# Wykonana.net
KiCad netlist of a schematic drawn in EAGLE
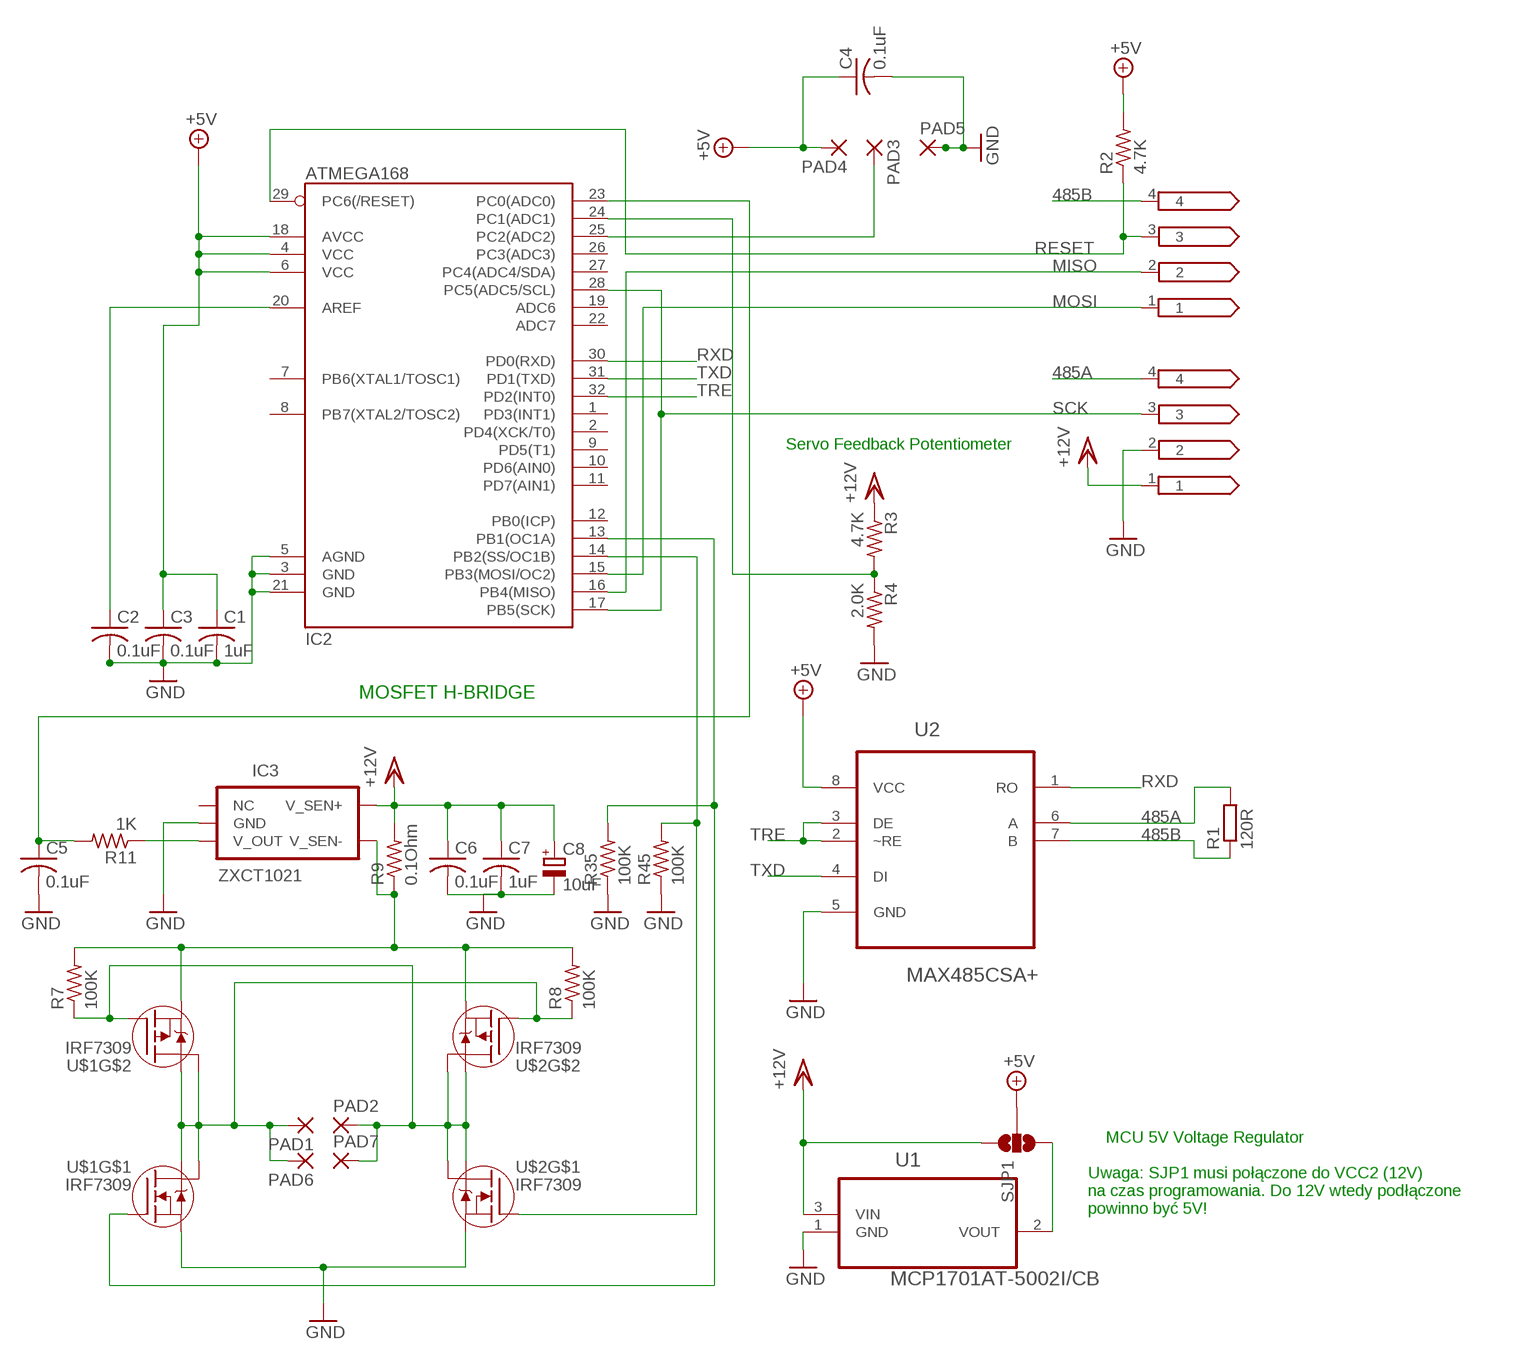
[diagram p0: schematic, sheet 1]

(export (version "E")
  (design (tool "Eeschema 10.0.6"))
  (components
    (comp (ref "C1")
      (value "1uF")
      (footprint "eagle-import:C0603")
      (libsource (lib "eagle-import") (part "C-USC0603"))
    )
    (comp (ref "C2")
      (value "0.1uF")
      (footprint "eagle-import:C0603")
      (libsource (lib "eagle-import") (part "C-USC0603"))
    )
    (comp (ref "C3")
      (value "0.1uF")
      (footprint "eagle-import:C0603")
      (libsource (lib "eagle-import") (part "C-USC0603"))
    )
    (comp (ref "C4")
      (value "0.1uF")
      (footprint "eagle-import:C0603")
      (libsource (lib "eagle-import") (part "C-USC0603"))
    )
    (comp (ref "C5")
      (value "0.1uF")
      (footprint "eagle-import:C0603K")
      (libsource (lib "eagle-import") (part "C-USC0603K"))
    )
    (comp (ref "C6")
      (value "0.1uF")
      (footprint "eagle-import:C0603")
      (libsource (lib "eagle-import") (part "C-USC0603"))
    )
    (comp (ref "C7")
      (value "1uF")
      (footprint "eagle-import:C0603")
      (libsource (lib "eagle-import") (part "C-USC0603"))
    )
    (comp (ref "C8")
      (value "10uF")
      (footprint "eagle-import:A_3216-18R")
      (libsource (lib "eagle-import") (part "CPOL-EUA/3216-18R"))
    )
    (comp (ref "IC2")
      (value "ATMEGA168")
      (footprint "eagle-import:TQFP32-08")
      (libsource (lib "eagle-import") (part "ATMEGA168"))
    )
    (comp (ref "IC3")
      (value "ZXCT1021")
      (footprint "eagle-import:SOT23-5")
      (libsource (lib "eagle-import") (part "ZXCT1021SOT23-5"))
    )
    (comp (ref "JP1")
      (value "4-EDGEVERSION2")
      (footprint "eagle-import:4-PIN-EDGE-V2")
      (libsource (lib "eagle-import") (part "4-EDGEVERSION2"))
    )
    (comp (ref "JP2")
      (value "4-EDGEVERSION2")
      (footprint "eagle-import:4-PIN-EDGE-V2")
      (libsource (lib "eagle-import") (part "4-EDGEVERSION2"))
    )
    (comp (ref "PAD1")
      (value "2,15/1,0")
      (footprint "eagle-import:2,15_1,0")
      (libsource (lib "eagle-import") (part "2,15/1,0"))
    )
    (comp (ref "PAD2")
      (value "2,15/1,0")
      (footprint "eagle-import:2,15_1,0")
      (libsource (lib "eagle-import") (part "2,15/1,0"))
    )
    (comp (ref "PAD3")
      (value "1,6/0,8")
      (footprint "eagle-import:1,6_0,8")
      (libsource (lib "eagle-import") (part "1,6/0,8"))
    )
    (comp (ref "PAD4")
      (value "1,6/0,8")
      (footprint "eagle-import:1,6_0,8")
      (libsource (lib "eagle-import") (part "1,6/0,8"))
    )
    (comp (ref "PAD5")
      (value "1,6/0,8")
      (footprint "eagle-import:1,6_0,8")
      (libsource (lib "eagle-import") (part "1,6/0,8"))
    )
    (comp (ref "PAD6")
      (value "2,15/1,0")
      (footprint "eagle-import:2,15_1,0")
      (libsource (lib "eagle-import") (part "2,15/1,0"))
    )
    (comp (ref "PAD7")
      (value "2,15/1,0")
      (footprint "eagle-import:2,15_1,0")
      (libsource (lib "eagle-import") (part "2,15/1,0"))
    )
    (comp (ref "R1")
      (value "120R")
      (footprint "eagle-import:R0603")
      (libsource (lib "eagle-import") (part "R-EU_R0603"))
    )
    (comp (ref "R2")
      (value "4.7K")
      (footprint "eagle-import:R0603")
      (libsource (lib "eagle-import") (part "R-US_R0603"))
    )
    (comp (ref "R3")
      (value "4.7K")
      (footprint "eagle-import:R0603")
      (libsource (lib "eagle-import") (part "R-US_R0603"))
    )
    (comp (ref "R4")
      (value "2.0K")
      (footprint "eagle-import:R0603")
      (libsource (lib "eagle-import") (part "R-US_R0603"))
    )
    (comp (ref "R7")
      (value "100K")
      (footprint "eagle-import:R0603")
      (libsource (lib "eagle-import") (part "R-US_R0603"))
    )
    (comp (ref "R8")
      (value "100K")
      (footprint "eagle-import:R0603")
      (libsource (lib "eagle-import") (part "R-US_R0603"))
    )
    (comp (ref "R9")
      (value "0.1Ohm")
      (footprint "eagle-import:R0603")
      (libsource (lib "eagle-import") (part "R-US_R0603"))
    )
    (comp (ref "R11")
      (value "1K")
      (footprint "eagle-import:R0603")
      (libsource (lib "eagle-import") (part "R-US_R0603"))
    )
    (comp (ref "R35")
      (value "100K")
      (footprint "eagle-import:R0603")
      (libsource (lib "eagle-import") (part "R-US_R0603"))
    )
    (comp (ref "R45")
      (value "100K")
      (footprint "eagle-import:R0603")
      (libsource (lib "eagle-import") (part "R-US_R0603"))
    )
    (comp (ref "SJP1")
      (value "SOLDERJUMPER_2WAYPASTE2&3")
      (footprint "eagle-import:SJ_3_PASTE2&3")
      (libsource (lib "eagle-import") (part "SOLDERJUMPER_2WAYPASTE2&3"))
    )
    (comp (ref "U$1")
      (value "IRF7309")
      (footprint "eagle-import:SO8-2")
      (libsource (lib "eagle-import") (part "IRF7309"))
    )
    (comp (ref "U$2")
      (value "IRF7309")
      (footprint "eagle-import:SO8-2")
      (libsource (lib "eagle-import") (part "IRF7309"))
    )
    (comp (ref "U1")
      (value "MCP1701AT-5002I/CB")
      (footprint "eagle-import:SOT95P255X145-3N")
      (libsource (lib "eagle-import") (part "MCP1701AT-5002I/CB"))
    )
    (comp (ref "U2")
      (value "MAX485CSA+")
      (footprint "eagle-import:SOIC127P600X175-8N")
      (libsource (lib "eagle-import") (part "MAX485CSA+"))
    )
  )
  (nets
    (net (code "1") (name "+5V") (class "Default")
      (node (ref "C1") (pin "1") (pinfunction "1_1") (pintype "passive"))
      (node (ref "C3") (pin "1") (pinfunction "1_1") (pintype "passive"))
      (node (ref "C4") (pin "1") (pinfunction "1_1") (pintype "passive"))
      (node (ref "IC2") (pin "18") (pinfunction "AVCC_18") (pintype "bidirectional"))
      (node (ref "IC2") (pin "4") (pinfunction "VCC_4") (pintype "bidirectional"))
      (node (ref "IC2") (pin "6") (pinfunction "VCC_6") (pintype "bidirectional"))
      (node (ref "PAD4") (pin "1") (pinfunction "P_1") (pintype "passive"))
      (node (ref "R2") (pin "2") (pinfunction "2_2") (pintype "passive"))
      (node (ref "SJP1") (pin "2") (pinfunction "2_2") (pintype "passive"))
      (node (ref "U2") (pin "8") (pinfunction "VCC_8") (pintype "power_in"))
    )
    (net (code "2") (name "+12V") (class "Default")
      (node (ref "C6") (pin "1") (pinfunction "1_1") (pintype "passive"))
      (node (ref "C7") (pin "1") (pinfunction "1_1") (pintype "passive"))
      (node (ref "C8") (pin "+") (pinfunction "+_+") (pintype "passive"))
      (node (ref "IC3") (pin "4") (pinfunction "V_SEN+_4") (pintype "input"))
      (node (ref "JP1") (pin "1") (pinfunction "1_1") (pintype "bidirectional"))
      (node (ref "R3") (pin "1") (pinfunction "1_1") (pintype "passive"))
      (node (ref "R9") (pin "2") (pinfunction "2_2") (pintype "passive"))
      (node (ref "SJP1") (pin "1") (pinfunction "1_1") (pintype "passive"))
      (node (ref "U1") (pin "3") (pinfunction "VIN_3") (pintype "input"))
    )
    (net (code "3") (name "/485A") (class "Default")
      (node (ref "JP1") (pin "4") (pinfunction "4_4") (pintype "bidirectional"))
      (node (ref "R1") (pin "2") (pinfunction "2_2") (pintype "passive"))
      (node (ref "U2") (pin "6") (pinfunction "A_6") (pintype "bidirectional"))
    )
    (net (code "4") (name "/485B") (class "Default")
      (node (ref "JP2") (pin "4") (pinfunction "4_4") (pintype "bidirectional"))
      (node (ref "R1") (pin "1") (pinfunction "1_1") (pintype "passive"))
      (node (ref "U2") (pin "7") (pinfunction "B_7") (pintype "bidirectional"))
    )
    (net (code "5") (name "/MISO") (class "Default")
      (node (ref "IC2") (pin "16") (pinfunction "PB4(MISO)_16") (pintype "bidirectional"))
      (node (ref "JP2") (pin "2") (pinfunction "2_2") (pintype "bidirectional"))
    )
    (net (code "6") (name "/MOSI") (class "Default")
      (node (ref "IC2") (pin "15") (pinfunction "PB3(MOSI/OC2)_15") (pintype "bidirectional"))
      (node (ref "JP2") (pin "1") (pinfunction "1_1") (pintype "bidirectional"))
    )
    (net (code "7") (name "/RESET") (class "Default")
      (node (ref "IC2") (pin "29") (pinfunction "PC6(/RESET)_29") (pintype "bidirectional"))
      (node (ref "JP2") (pin "3") (pinfunction "3_3") (pintype "bidirectional"))
      (node (ref "R2") (pin "1") (pinfunction "1_1") (pintype "passive"))
    )
    (net (code "8") (name "/RXD") (class "Default")
      (node (ref "IC2") (pin "30") (pinfunction "PD0(RXD)_30") (pintype "bidirectional"))
      (node (ref "U2") (pin "1") (pinfunction "RO_1") (pintype "output"))
    )
    (net (code "9") (name "/SCK") (class "Default")
      (node (ref "IC2") (pin "17") (pinfunction "PB5(SCK)_17") (pintype "bidirectional"))
      (node (ref "IC2") (pin "28") (pinfunction "PC5(ADC5/SCL)_28") (pintype "bidirectional"))
      (node (ref "JP1") (pin "3") (pinfunction "3_3") (pintype "bidirectional"))
    )
    (net (code "10") (name "/TRE") (class "Default")
      (node (ref "IC2") (pin "32") (pinfunction "PD2(INT0)_32") (pintype "bidirectional"))
      (node (ref "U2") (pin "2") (pinfunction "~{RE}_2") (pintype "input"))
      (node (ref "U2") (pin "3") (pinfunction "DE_3") (pintype "input"))
    )
    (net (code "11") (name "/TXD") (class "Default")
      (node (ref "IC2") (pin "31") (pinfunction "PD1(TXD)_31") (pintype "bidirectional"))
      (node (ref "U2") (pin "4") (pinfunction "DI_4") (pintype "input"))
    )
    (net (code "12") (name "GND") (class "Default")
      (node (ref "C1") (pin "2") (pinfunction "2_2") (pintype "passive"))
      (node (ref "C2") (pin "2") (pinfunction "2_2") (pintype "passive"))
      (node (ref "C3") (pin "2") (pinfunction "2_2") (pintype "passive"))
      (node (ref "C4") (pin "2") (pinfunction "2_2") (pintype "passive"))
      (node (ref "C5") (pin "2") (pinfunction "2_2") (pintype "passive"))
      (node (ref "C6") (pin "2") (pinfunction "2_2") (pintype "passive"))
      (node (ref "C7") (pin "2") (pinfunction "2_2") (pintype "passive"))
      (node (ref "C8") (pin "-") (pinfunction "-_-") (pintype "passive"))
      (node (ref "IC2") (pin "21") (pinfunction "GND_21") (pintype "bidirectional"))
      (node (ref "IC2") (pin "3") (pinfunction "GND_3") (pintype "bidirectional"))
      (node (ref "IC2") (pin "5") (pinfunction "AGND_5") (pintype "bidirectional"))
      (node (ref "IC3") (pin "2") (pinfunction "GND_2") (pintype "input"))
      (node (ref "JP1") (pin "2") (pinfunction "2_2") (pintype "bidirectional"))
      (node (ref "PAD5") (pin "1") (pinfunction "P_1") (pintype "passive"))
      (node (ref "R35") (pin "1") (pinfunction "1_1") (pintype "passive"))
      (node (ref "R4") (pin "2") (pinfunction "2_2") (pintype "passive"))
      (node (ref "R45") (pin "1") (pinfunction "1_1") (pintype "passive"))
      (node (ref "U$1") (pin "1") (pinfunction "S_1") (pintype "bidirectional"))
      (node (ref "U$2") (pin "1") (pinfunction "S_1") (pintype "bidirectional"))
      (node (ref "U1") (pin "1") (pinfunction "GND_1") (pintype "passive"))
      (node (ref "U2") (pin "5") (pinfunction "GND_5") (pintype "passive"))
    )
    (net (code "13") (name "Net-(IC2-AREF)") (class "Default")
      (node (ref "C2") (pin "1") (pinfunction "1_1") (pintype "passive"))
      (node (ref "IC2") (pin "20") (pinfunction "AREF_20") (pintype "bidirectional"))
    )
    (net (code "14") (name "Net-(IC2-PB1(OC1A))") (class "Default")
      (node (ref "IC2") (pin "13") (pinfunction "PB1(OC1A)_13") (pintype "bidirectional"))
      (node (ref "R35") (pin "2") (pinfunction "2_2") (pintype "passive"))
      (node (ref "U$1") (pin "2") (pinfunction "G_2") (pintype "bidirectional"))
    )
    (net (code "15") (name "Net-(IC2-PB2(SS{slash}OC1B))") (class "Default")
      (node (ref "IC2") (pin "14") (pinfunction "PB2(SS/OC1B)_14") (pintype "bidirectional"))
      (node (ref "R45") (pin "2") (pinfunction "2_2") (pintype "passive"))
      (node (ref "U$2") (pin "2") (pinfunction "G_2") (pintype "bidirectional"))
    )
    (net (code "16") (name "Net-(IC2-PC0(ADC0))") (class "Default")
      (node (ref "C5") (pin "1") (pinfunction "1_1") (pintype "passive"))
      (node (ref "IC2") (pin "23") (pinfunction "PC0(ADC0)_23") (pintype "bidirectional"))
      (node (ref "R11") (pin "2") (pinfunction "2_2") (pintype "passive"))
    )
    (net (code "17") (name "Net-(IC2-PC1(ADC1))") (class "Default")
      (node (ref "IC2") (pin "24") (pinfunction "PC1(ADC1)_24") (pintype "bidirectional"))
      (node (ref "R3") (pin "2") (pinfunction "2_2") (pintype "passive"))
      (node (ref "R4") (pin "1") (pinfunction "1_1") (pintype "passive"))
    )
    (net (code "18") (name "Net-(IC2-PC2(ADC2))") (class "Default")
      (node (ref "IC2") (pin "25") (pinfunction "PC2(ADC2)_25") (pintype "bidirectional"))
      (node (ref "PAD3") (pin "1") (pinfunction "P_1") (pintype "passive"))
    )
    (net (code "19") (name "Net-(IC3-V_OUT)") (class "Default")
      (node (ref "IC3") (pin "3") (pinfunction "V_OUT_3") (pintype "input"))
      (node (ref "R11") (pin "1") (pinfunction "1_1") (pintype "passive"))
    )
    (net (code "20") (name "Net-(IC3-V_SEN-)") (class "Default")
      (node (ref "IC3") (pin "5") (pinfunction "V_SEN-_5") (pintype "passive"))
      (node (ref "R7") (pin "2") (pinfunction "2_2") (pintype "passive"))
      (node (ref "R8") (pin "2") (pinfunction "2_2") (pintype "passive"))
      (node (ref "R9") (pin "1") (pinfunction "1_1") (pintype "passive"))
      (node (ref "U$1") (pin "3") (pinfunction "S_3") (pintype "bidirectional"))
      (node (ref "U$2") (pin "3") (pinfunction "S_3") (pintype "bidirectional"))
    )
    (net (code "21") (name "Net-(PAD1-P)") (class "Default")
      (node (ref "PAD1") (pin "1") (pinfunction "P_1") (pintype "passive"))
      (node (ref "PAD6") (pin "1") (pinfunction "P_1") (pintype "passive"))
      (node (ref "R8") (pin "1") (pinfunction "1_1") (pintype "passive"))
      (node (ref "U$1") (pin "5") (pinfunction "D_5") (pintype "bidirectional"))
      (node (ref "U$1") (pin "6") (pinfunction "D_6") (pintype "bidirectional"))
      (node (ref "U$1") (pin "7") (pinfunction "D_7") (pintype "bidirectional"))
      (node (ref "U$1") (pin "8") (pinfunction "D_8") (pintype "bidirectional"))
      (node (ref "U$2") (pin "4") (pinfunction "G_4") (pintype "bidirectional"))
    )
    (net (code "22") (name "Net-(PAD2-P)") (class "Default")
      (node (ref "PAD2") (pin "1") (pinfunction "P_1") (pintype "passive"))
      (node (ref "PAD7") (pin "1") (pinfunction "P_1") (pintype "passive"))
      (node (ref "R7") (pin "1") (pinfunction "1_1") (pintype "passive"))
      (node (ref "U$1") (pin "4") (pinfunction "G_4") (pintype "bidirectional"))
      (node (ref "U$2") (pin "5") (pinfunction "D_5") (pintype "bidirectional"))
      (node (ref "U$2") (pin "6") (pinfunction "D_6") (pintype "bidirectional"))
      (node (ref "U$2") (pin "7") (pinfunction "D_7") (pintype "bidirectional"))
      (node (ref "U$2") (pin "8") (pinfunction "D_8") (pintype "bidirectional"))
    )
    (net (code "23") (name "Net-(U1-VOUT)") (class "Default")
      (node (ref "SJP1") (pin "3") (pinfunction "3_3") (pintype "passive"))
      (node (ref "U1") (pin "2") (pinfunction "VOUT_2") (pintype "output"))
    )
    (net (code "24") (name "unconnected-(IC2-ADC6-Pad19)") (class "Default")
      (node (ref "IC2") (pin "19") (pinfunction "ADC6_19") (pintype "bidirectional"))
    )
    (net (code "25") (name "unconnected-(IC2-ADC7-Pad22)") (class "Default")
      (node (ref "IC2") (pin "22") (pinfunction "ADC7_22") (pintype "bidirectional"))
    )
    (net (code "26") (name "unconnected-(IC2-PB0(ICP)-Pad12)") (class "Default")
      (node (ref "IC2") (pin "12") (pinfunction "PB0(ICP)_12") (pintype "bidirectional"))
    )
    (net (code "27") (name "unconnected-(IC2-PB6(XTAL1{slash}TOSC1)-Pad7)") (class "Default")
      (node (ref "IC2") (pin "7") (pinfunction "PB6(XTAL1/TOSC1)_7") (pintype "bidirectional"))
    )
    (net (code "28") (name "unconnected-(IC2-PB7(XTAL2{slash}TOSC2)-Pad8)") (class "Default")
      (node (ref "IC2") (pin "8") (pinfunction "PB7(XTAL2/TOSC2)_8") (pintype "bidirectional"))
    )
    (net (code "29") (name "unconnected-(IC2-PC3(ADC3)-Pad26)") (class "Default")
      (node (ref "IC2") (pin "26") (pinfunction "PC3(ADC3)_26") (pintype "bidirectional"))
    )
    (net (code "30") (name "unconnected-(IC2-PC4(ADC4{slash}SDA)-Pad27)") (class "Default")
      (node (ref "IC2") (pin "27") (pinfunction "PC4(ADC4/SDA)_27") (pintype "bidirectional"))
    )
    (net (code "31") (name "unconnected-(IC2-PD3(INT1)-Pad1)") (class "Default")
      (node (ref "IC2") (pin "1") (pinfunction "PD3(INT1)_1") (pintype "bidirectional"))
    )
    (net (code "32") (name "unconnected-(IC2-PD4(XCK{slash}T0)-Pad2)") (class "Default")
      (node (ref "IC2") (pin "2") (pinfunction "PD4(XCK/T0)_2") (pintype "bidirectional"))
    )
    (net (code "33") (name "unconnected-(IC2-PD5(T1)-Pad9)") (class "Default")
      (node (ref "IC2") (pin "9") (pinfunction "PD5(T1)_9") (pintype "bidirectional"))
    )
    (net (code "34") (name "unconnected-(IC2-PD6(AIN0)-Pad10)") (class "Default")
      (node (ref "IC2") (pin "10") (pinfunction "PD6(AIN0)_10") (pintype "bidirectional"))
    )
    (net (code "35") (name "unconnected-(IC2-PD7(AIN1)-Pad11)") (class "Default")
      (node (ref "IC2") (pin "11") (pinfunction "PD7(AIN1)_11") (pintype "bidirectional"))
    )
    (net (code "36") (name "unconnected-(IC3-NC-Pad1)") (class "Default")
      (node (ref "IC3") (pin "1") (pinfunction "NC_1") (pintype "no_connect"))
    )
  )
)
